# EEG.net
KiCad netlist of a schematic drawn in EAGLE
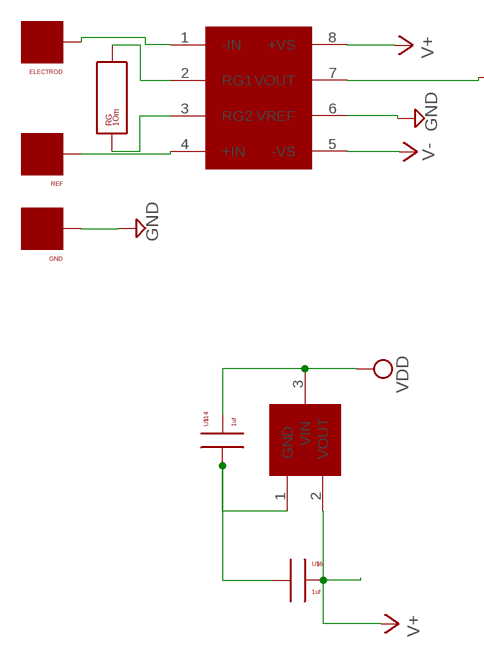
[diagram p0: schematic, sheet 1, part 1 of 2]
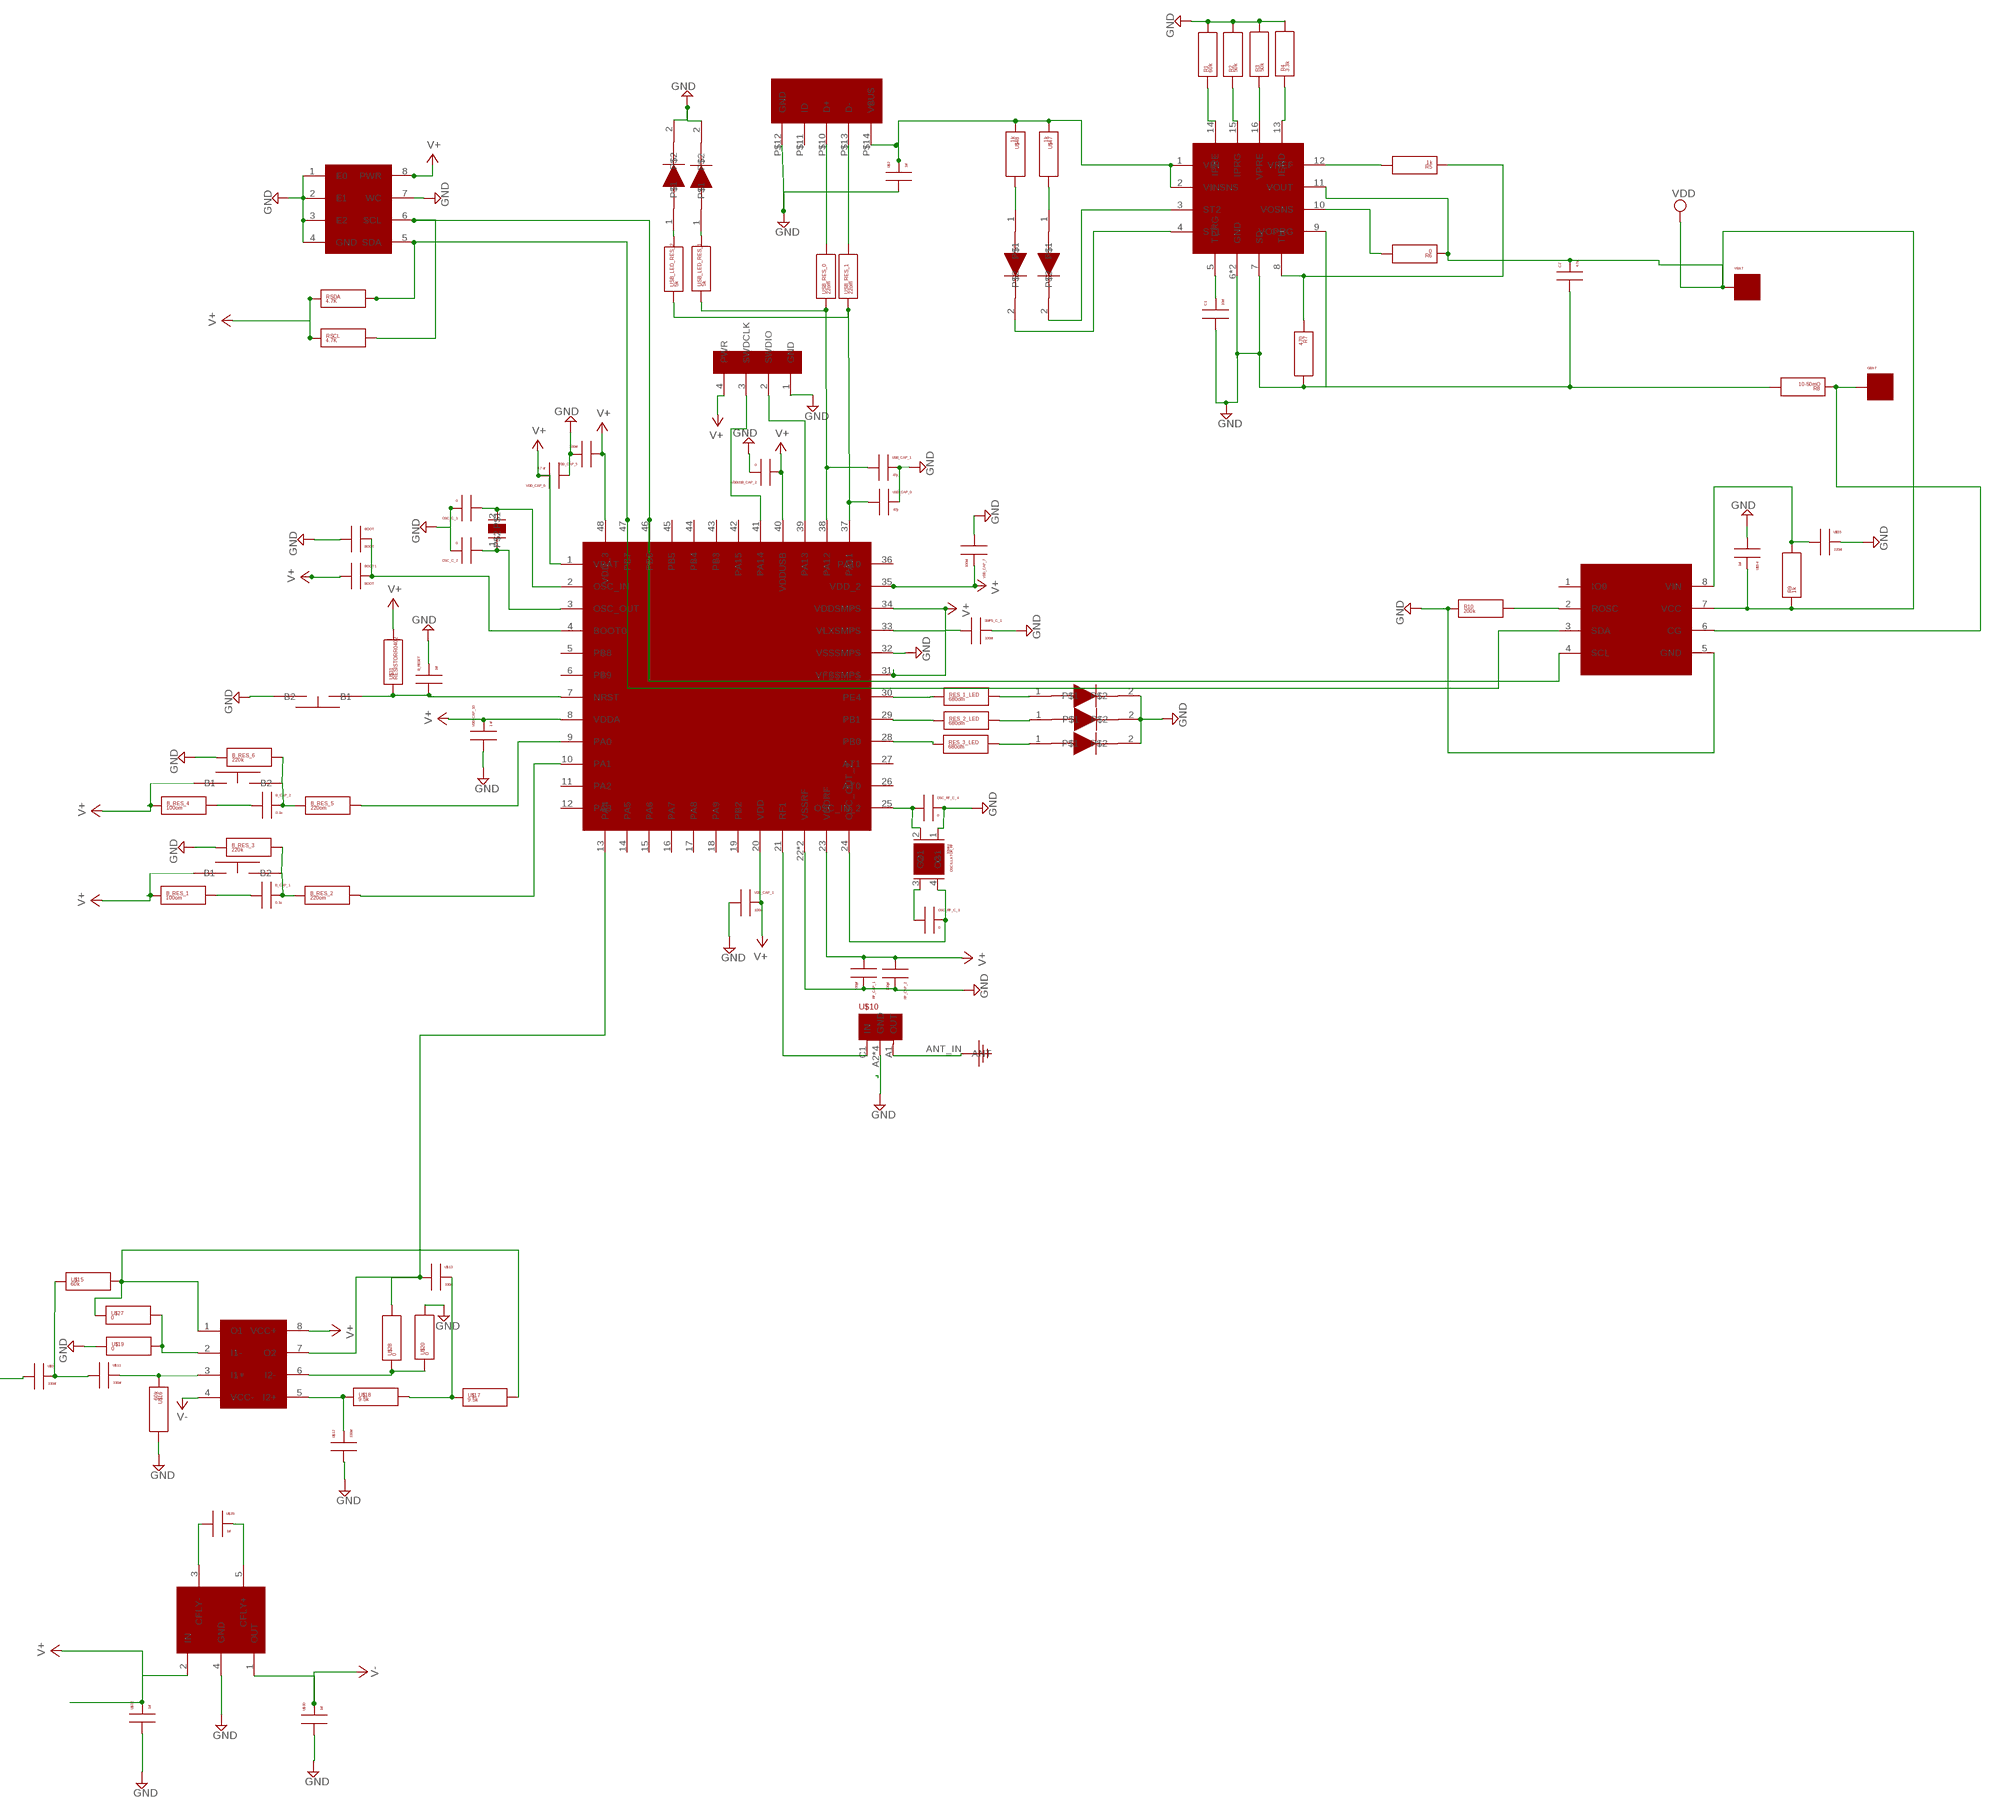
[diagram p1: schematic, sheet 1, part 2 of 2]

(export (version "E")
  (design (tool "Eeschema 10.0.6"))
  (components
    (comp (ref "BOOT")
      (value "BOOT")
      (footprint "eagle-import:C0402")
      (libsource (lib "eagle-import") (part "CAPACITORC0402"))
    )
    (comp (ref "BOOT1")
      (value "BOOT")
      (footprint "eagle-import:C0402")
      (libsource (lib "eagle-import") (part "CAPACITORC0402"))
    )
    (comp (ref "BUTTON1")
      (value "BUTTON")
      (footprint "eagle-import:BUTTON")
      (libsource (lib "eagle-import") (part "BUTTON"))
    )
    (comp (ref "BUTTON2")
      (value "BUTTON")
      (footprint "eagle-import:BUTTON")
      (libsource (lib "eagle-import") (part "BUTTON"))
    )
    (comp (ref "B_CAP_1")
      (value "0.1u")
      (footprint "eagle-import:C0402")
      (libsource (lib "eagle-import") (part "CAPACITORC0402"))
    )
    (comp (ref "B_CAP_2")
      (value "0.1u")
      (footprint "eagle-import:C0402")
      (libsource (lib "eagle-import") (part "CAPACITORC0402"))
    )
    (comp (ref "B_RESET")
      (value "1uf")
      (footprint "eagle-import:C0402")
      (libsource (lib "eagle-import") (part "CAPACITORC0402"))
    )
    (comp (ref "B_RES_1")
      (value "100om")
      (footprint "eagle-import:R0402")
      (libsource (lib "eagle-import") (part "RESISTORR0402"))
    )
    (comp (ref "B_RES_2")
      (value "220om")
      (footprint "eagle-import:R0402")
      (libsource (lib "eagle-import") (part "RESISTORR0402"))
    )
    (comp (ref "B_RES_3")
      (value "220k")
      (footprint "eagle-import:R0402")
      (libsource (lib "eagle-import") (part "RESISTORR0402"))
    )
    (comp (ref "B_RES_4")
      (value "100om")
      (footprint "eagle-import:R0402")
      (libsource (lib "eagle-import") (part "RESISTORR0402"))
    )
    (comp (ref "B_RES_5")
      (value "220om")
      (footprint "eagle-import:R0402")
      (libsource (lib "eagle-import") (part "RESISTORR0402"))
    )
    (comp (ref "B_RES_6")
      (value "220k")
      (footprint "eagle-import:R0402")
      (libsource (lib "eagle-import") (part "RESISTORR0402"))
    )
    (comp (ref "C1")
      (value "10nf")
      (footprint "eagle-import:C0402")
      (libsource (lib "eagle-import") (part "CAPACITORC0402"))
    )
    (comp (ref "C2")
      (value "4.7uf")
      (footprint "eagle-import:C0402")
      (libsource (lib "eagle-import") (part "CAPACITORC0402"))
    )
    (comp (ref "ELECTROD")
      (value "PIN-1")
      (footprint "eagle-import:PIN-1")
      (libsource (lib "eagle-import") (part "PIN-1"))
    )
    (comp (ref "GBAT")
      (value "PIN-1")
      (footprint "eagle-import:PIN-1")
      (libsource (lib "eagle-import") (part "PIN-1"))
    )
    (comp (ref "GND")
      (value "PIN-1")
      (footprint "eagle-import:PIN-1")
      (libsource (lib "eagle-import") (part "PIN-1"))
    )
    (comp (ref "LED_1")
      (value "LED")
      (footprint "eagle-import:R0402")
      (libsource (lib "eagle-import") (part "LED"))
    )
    (comp (ref "LED_2")
      (value "LED")
      (footprint "eagle-import:R0402")
      (libsource (lib "eagle-import") (part "LED"))
    )
    (comp (ref "LED_3")
      (value "LED")
      (footprint "eagle-import:R0402")
      (libsource (lib "eagle-import") (part "LED"))
    )
    (comp (ref "OSCILLATOR_RF")
      (value "32mhz")
      (footprint "eagle-import:NX2520SA")
      (libsource (lib "eagle-import") (part "NX2520SA"))
    )
    (comp (ref "OSC_C_1")
      (value "0")
      (footprint "eagle-import:C0402")
      (libsource (lib "eagle-import") (part "CAPACITORC0402"))
    )
    (comp (ref "OSC_C_2")
      (value "0")
      (footprint "eagle-import:C0402")
      (libsource (lib "eagle-import") (part "CAPACITORC0402"))
    )
    (comp (ref "OSC_RF_C_3")
      (value "0")
      (footprint "eagle-import:C0402")
      (libsource (lib "eagle-import") (part "CAPACITORC0402"))
    )
    (comp (ref "OSC_RF_C_4")
      (value "0")
      (footprint "eagle-import:C0402")
      (libsource (lib "eagle-import") (part "CAPACITORC0402"))
    )
    (comp (ref "R1")
      (value "60k")
      (footprint "eagle-import:R0402")
      (libsource (lib "eagle-import") (part "RESISTORR0402"))
    )
    (comp (ref "R2")
      (value "50k")
      (footprint "eagle-import:R0402")
      (libsource (lib "eagle-import") (part "RESISTORR0402"))
    )
    (comp (ref "R3")
      (value "50k")
      (footprint "eagle-import:R0402")
      (libsource (lib "eagle-import") (part "RESISTORR0402"))
    )
    (comp (ref "R4")
      (value "3.3k")
      (footprint "eagle-import:R0402")
      (libsource (lib "eagle-import") (part "RESISTORR0402"))
    )
    (comp (ref "R5")
      (value "1k")
      (footprint "eagle-import:R0402")
      (libsource (lib "eagle-import") (part "RESISTORR0402"))
    )
    (comp (ref "R6")
      (value "0")
      (footprint "eagle-import:R0402")
      (libsource (lib "eagle-import") (part "RESISTORR0402"))
    )
    (comp (ref "R7")
      (value "470")
      (footprint "eagle-import:R0402")
      (libsource (lib "eagle-import") (part "RESISTORR0402"))
    )
    (comp (ref "R8")
      (value "10-50mO")
      (footprint "eagle-import:R0402")
      (libsource (lib "eagle-import") (part "RESISTORR0402"))
    )
    (comp (ref "R9")
      (value "1k")
      (footprint "eagle-import:R0402")
      (libsource (lib "eagle-import") (part "RESISTORR0402"))
    )
    (comp (ref "R10")
      (value "200k")
      (footprint "eagle-import:R0402")
      (libsource (lib "eagle-import") (part "RESISTORR0402"))
    )
    (comp (ref "REF")
      (value "PIN-1")
      (footprint "eagle-import:PIN-1")
      (libsource (lib "eagle-import") (part "PIN-1"))
    )
    (comp (ref "RES_1_LED")
      (value "680om")
      (footprint "eagle-import:R0402")
      (libsource (lib "eagle-import") (part "RESISTORR0402"))
    )
    (comp (ref "RES_2_LED")
      (value "680om")
      (footprint "eagle-import:R0402")
      (libsource (lib "eagle-import") (part "RESISTORR0402"))
    )
    (comp (ref "RES_3_LED")
      (value "680om")
      (footprint "eagle-import:R0402")
      (libsource (lib "eagle-import") (part "RESISTORR0402"))
    )
    (comp (ref "RF_CAP_1")
      (value "100pf")
      (footprint "eagle-import:C0402")
      (libsource (lib "eagle-import") (part "CAPACITORC0402"))
    )
    (comp (ref "RF_CAP_2")
      (value "100pf")
      (footprint "eagle-import:C0402")
      (libsource (lib "eagle-import") (part "CAPACITORC0402"))
    )
    (comp (ref "RG")
      (value "1Om")
      (footprint "eagle-import:R0402")
      (libsource (lib "eagle-import") (part "RESISTORR0402"))
    )
    (comp (ref "RSCL")
      (value "4.7K")
      (footprint "eagle-import:R0402")
      (libsource (lib "eagle-import") (part "RESISTORR0402"))
    )
    (comp (ref "RSDA")
      (value "4.7K")
      (footprint "eagle-import:R0402")
      (libsource (lib "eagle-import") (part "RESISTORR0402"))
    )
    (comp (ref "SMPS_C_1")
      (value "100nf")
      (footprint "eagle-import:C0402")
      (libsource (lib "eagle-import") (part "CAPACITORC0402"))
    )
    (comp (ref "U$1")
      (value "STM32WB55")
      (footprint "eagle-import:STM32WB55")
      (libsource (lib "eagle-import") (part "STM32WB55"))
    )
    (comp (ref "U$2")
      (value "1uf")
      (footprint "eagle-import:C0402")
      (libsource (lib "eagle-import") (part "CAPACITORC0402"))
    )
    (comp (ref "U$3")
      (value "ANT")
      (footprint "eagle-import:ANT")
      (libsource (lib "eagle-import") (part "ANT"))
    )
    (comp (ref "U$4")
      (value "AD8422")
      (footprint "eagle-import:AD8422")
      (libsource (lib "eagle-import") (part "AD8422"))
    )
    (comp (ref "U$5")
      (value "TPS60403")
      (footprint "eagle-import:TPS60403")
      (libsource (lib "eagle-import") (part "TPS60403"))
    )
    (comp (ref "U$6")
      (value "1uf")
      (footprint "eagle-import:C0402")
      (libsource (lib "eagle-import") (part "CAPACITORC0402"))
    )
    (comp (ref "U$7")
      (value "LM358")
      (footprint "eagle-import:LM358")
      (libsource (lib "eagle-import") (part "LM358"))
    )
    (comp (ref "U$8")
      (value "MCP1703")
      (footprint "eagle-import:MCP1703")
      (libsource (lib "eagle-import") (part "MCP1703"))
    )
    (comp (ref "U$9")
      (value "330nf")
      (footprint "eagle-import:C0402")
      (libsource (lib "eagle-import") (part "CAPACITORC0402"))
    )
    (comp (ref "U$10")
      (value "MLPF-WB55-01E3DEFAULT")
      (footprint "eagle-import:MLPF-WB55-01E3")
      (libsource (lib "eagle-import") (part "MLPF-WB55-01E3DEFAULT"))
    )
    (comp (ref "U$11")
      (value "330nf")
      (footprint "eagle-import:C0402")
      (libsource (lib "eagle-import") (part "CAPACITORC0402"))
    )
    (comp (ref "U$12")
      (value "330nf")
      (footprint "eagle-import:C0402")
      (libsource (lib "eagle-import") (part "CAPACITORC0402"))
    )
    (comp (ref "U$13")
      (value "330nf")
      (footprint "eagle-import:C0402")
      (libsource (lib "eagle-import") (part "CAPACITORC0402"))
    )
    (comp (ref "U$14")
      (value "1uf")
      (footprint "eagle-import:C0402")
      (libsource (lib "eagle-import") (part "CAPACITORC0402"))
    )
    (comp (ref "U$15")
      (value "60k")
      (footprint "eagle-import:R0402")
      (libsource (lib "eagle-import") (part "RESISTORR0402"))
    )
    (comp (ref "U$16")
      (value "60k")
      (footprint "eagle-import:R0402")
      (libsource (lib "eagle-import") (part "RESISTORR0402"))
    )
    (comp (ref "U$17")
      (value "9.5k")
      (footprint "eagle-import:R0402")
      (libsource (lib "eagle-import") (part "RESISTORR0402"))
    )
    (comp (ref "U$18")
      (value "9.5k")
      (footprint "eagle-import:R0402")
      (libsource (lib "eagle-import") (part "RESISTORR0402"))
    )
    (comp (ref "U$19")
      (value "0")
      (footprint "eagle-import:R0402")
      (libsource (lib "eagle-import") (part "RESISTORR0402"))
    )
    (comp (ref "U$20")
      (value "0")
      (footprint "eagle-import:R0402")
      (libsource (lib "eagle-import") (part "RESISTORR0402"))
    )
    (comp (ref "U$21")
      (value "M24M01")
      (footprint "eagle-import:M24M01")
      (libsource (lib "eagle-import") (part "M24M01"))
    )
    (comp (ref "U$22")
      (value "USBUSBT")
      (footprint "eagle-import:USBT")
      (libsource (lib "eagle-import") (part "USBUSBT"))
    )
    (comp (ref "U$23")
      (value "SWDSWDD")
      (footprint "eagle-import:SWD")
      (libsource (lib "eagle-import") (part "SWDSWDD"))
    )
    (comp (ref "U$24")
      (value "STC3100")
      (footprint "eagle-import:STC3100")
      (libsource (lib "eagle-import") (part "STC3100"))
    )
    (comp (ref "U$25")
      (value "L6924D")
      (footprint "eagle-import:L6924D")
      (libsource (lib "eagle-import") (part "L6924D"))
    )
    (comp (ref "U$26")
      (value "BUTTON")
      (footprint "eagle-import:BUTTON")
      (libsource (lib "eagle-import") (part "BUTTON"))
    )
    (comp (ref "U$27")
      (value "0")
      (footprint "eagle-import:R0402")
      (libsource (lib "eagle-import") (part "RESISTORR0402"))
    )
    (comp (ref "U$28")
      (value "0")
      (footprint "eagle-import:R0402")
      (libsource (lib "eagle-import") (part "RESISTORR0402"))
    )
    (comp (ref "U$29")
      (value "1uf")
      (footprint "eagle-import:C0402")
      (libsource (lib "eagle-import") (part "CAPACITORC0402"))
    )
    (comp (ref "U$30")
      (value "1uf")
      (footprint "eagle-import:C0402")
      (libsource (lib "eagle-import") (part "CAPACITORC0402"))
    )
    (comp (ref "U$31")
      (value "RESISTORR0402")
      (footprint "eagle-import:R0402")
      (libsource (lib "eagle-import") (part "RESISTORR0402"))
    )
    (comp (ref "U$32")
      (value "1uf")
      (footprint "eagle-import:C0402")
      (libsource (lib "eagle-import") (part "CAPACITORC0402"))
    )
    (comp (ref "U$33")
      (value "OSC_32KH")
      (footprint "eagle-import:RESM2012X60N")
      (libsource (lib "eagle-import") (part "OSC_32KH"))
    )
    (comp (ref "U$47")
      (value "1k")
      (footprint "eagle-import:R0402")
      (libsource (lib "eagle-import") (part "RESISTORR0402"))
    )
    (comp (ref "U$48")
      (value "1k")
      (footprint "eagle-import:R0402")
      (libsource (lib "eagle-import") (part "RESISTORR0402"))
    )
    (comp (ref "U$49")
      (value "LED")
      (footprint "eagle-import:R0402")
      (libsource (lib "eagle-import") (part "LED"))
    )
    (comp (ref "U$50")
      (value "LED")
      (footprint "eagle-import:R0402")
      (libsource (lib "eagle-import") (part "LED"))
    )
    (comp (ref "U$54")
      (value "1uf")
      (footprint "eagle-import:C0402")
      (libsource (lib "eagle-import") (part "CAPACITORC0402"))
    )
    (comp (ref "U$55")
      (value "220nf")
      (footprint "eagle-import:C0402")
      (libsource (lib "eagle-import") (part "CAPACITORC0402"))
    )
    (comp (ref "USB_CAP_0")
      (value "47p")
      (footprint "eagle-import:C0402")
      (libsource (lib "eagle-import") (part "CAPACITORC0402"))
    )
    (comp (ref "USB_CAP_1")
      (value "47p")
      (footprint "eagle-import:C0402")
      (libsource (lib "eagle-import") (part "CAPACITORC0402"))
    )
    (comp (ref "USB_LED_1")
      (value "LED")
      (footprint "eagle-import:R0402")
      (libsource (lib "eagle-import") (part "LED"))
    )
    (comp (ref "USB_LED_2")
      (value "LED")
      (footprint "eagle-import:R0402")
      (libsource (lib "eagle-import") (part "LED"))
    )
    (comp (ref "USB_LED_RES_1")
      (value "5k")
      (footprint "eagle-import:R0402")
      (libsource (lib "eagle-import") (part "RESISTORR0402"))
    )
    (comp (ref "USB_LED_RES_2")
      (value "5k")
      (footprint "eagle-import:R0402")
      (libsource (lib "eagle-import") (part "RESISTORR0402"))
    )
    (comp (ref "USB_RES_0")
      (value "22om")
      (footprint "eagle-import:R0402")
      (libsource (lib "eagle-import") (part "RESISTORR0402"))
    )
    (comp (ref "USB_RES_1")
      (value "22om")
      (footprint "eagle-import:R0402")
      (libsource (lib "eagle-import") (part "RESISTORR0402"))
    )
    (comp (ref "VBAT")
      (value "PIN-1")
      (footprint "eagle-import:PIN-1")
      (libsource (lib "eagle-import") (part "PIN-1"))
    )
    (comp (ref "VDDUSB_CAP_2")
      (value "0")
      (footprint "eagle-import:C0402")
      (libsource (lib "eagle-import") (part "CAPACITORC0402"))
    )
    (comp (ref "VDD_CAP_1")
      (value "100nf")
      (footprint "eagle-import:C0402")
      (libsource (lib "eagle-import") (part "CAPACITORC0402"))
    )
    (comp (ref "VDD_CAP_5")
      (value "100nf")
      (footprint "eagle-import:C0402")
      (libsource (lib "eagle-import") (part "CAPACITORC0402"))
    )
    (comp (ref "VDD_CAP_6")
      (value "4.7 uf")
      (footprint "eagle-import:C0402")
      (libsource (lib "eagle-import") (part "CAPACITORC0402"))
    )
    (comp (ref "VDD_CAP_7")
      (value "100nf")
      (footprint "eagle-import:C0402")
      (libsource (lib "eagle-import") (part "CAPACITORC0402"))
    )
    (comp (ref "VDD_CAP_10")
      (value "1 uf")
      (footprint "eagle-import:C0402")
      (libsource (lib "eagle-import") (part "CAPACITORC0402"))
    )
  )
  (nets
    (net (code "1") (name "GND") (class "Default")
      (node (ref "BOOT") (pin "1") (pinfunction "1_1") (pintype "bidirectional"))
      (node (ref "B_RESET") (pin "2") (pinfunction "2_2") (pintype "bidirectional"))
      (node (ref "B_RES_3") (pin "1") (pinfunction "1_1") (pintype "bidirectional"))
      (node (ref "B_RES_6") (pin "1") (pinfunction "1_1") (pintype "bidirectional"))
      (node (ref "C1") (pin "1") (pinfunction "1_1") (pintype "bidirectional"))
      (node (ref "C2") (pin "1") (pinfunction "1_1") (pintype "bidirectional"))
      (node (ref "GND") (pin "P$1") (pinfunction "PIN_P$1") (pintype "bidirectional"))
      (node (ref "LED_1") (pin "2") (pinfunction "P$2_2") (pintype "bidirectional"))
      (node (ref "LED_2") (pin "2") (pinfunction "P$2_2") (pintype "bidirectional"))
      (node (ref "LED_3") (pin "2") (pinfunction "P$2_2") (pintype "bidirectional"))
      (node (ref "OSCILLATOR_RF") (pin "1") (pinfunction "G1_1") (pintype "bidirectional"))
      (node (ref "OSC_C_1") (pin "2") (pinfunction "2_2") (pintype "bidirectional"))
      (node (ref "OSC_C_2") (pin "2") (pinfunction "2_2") (pintype "bidirectional"))
      (node (ref "OSC_RF_C_4") (pin "2") (pinfunction "2_2") (pintype "bidirectional"))
      (node (ref "R1") (pin "2") (pinfunction "2_2") (pintype "bidirectional"))
      (node (ref "R10") (pin "1") (pinfunction "1_1") (pintype "bidirectional"))
      (node (ref "R2") (pin "2") (pinfunction "2_2") (pintype "bidirectional"))
      (node (ref "R3") (pin "2") (pinfunction "2_2") (pintype "bidirectional"))
      (node (ref "R4") (pin "2") (pinfunction "2_2") (pintype "bidirectional"))
      (node (ref "R7") (pin "2") (pinfunction "2_2") (pintype "bidirectional"))
      (node (ref "R8") (pin "2") (pinfunction "2_2") (pintype "bidirectional"))
      (node (ref "RF_CAP_1") (pin "2") (pinfunction "2_2") (pintype "bidirectional"))
      (node (ref "RF_CAP_2") (pin "2") (pinfunction "2_2") (pintype "bidirectional"))
      (node (ref "SMPS_C_1") (pin "2") (pinfunction "2_2") (pintype "bidirectional"))
      (node (ref "U$1") (pin "22") (pinfunction "VSSRF_22") (pintype "bidirectional"))
      (node (ref "U$1") (pin "32") (pinfunction "VSSSMPS_32") (pintype "bidirectional"))
      (node (ref "U$1") (pin "49") (pinfunction "VSSRF_49") (pintype "bidirectional"))
      (node (ref "U$10") (pin "A2") (pinfunction "GND_A2") (pintype "bidirectional"))
      (node (ref "U$10") (pin "B1") (pinfunction "GND_B1") (pintype "bidirectional"))
      (node (ref "U$10") (pin "B2") (pinfunction "GND_B2") (pintype "bidirectional"))
      (node (ref "U$10") (pin "C2") (pinfunction "GND_C2") (pintype "bidirectional"))
      (node (ref "U$12") (pin "1") (pinfunction "1_1") (pintype "bidirectional"))
      (node (ref "U$16") (pin "2") (pinfunction "2_2") (pintype "bidirectional"))
      (node (ref "U$19") (pin "1") (pinfunction "1_1") (pintype "bidirectional"))
      (node (ref "U$2") (pin "1") (pinfunction "1_1") (pintype "bidirectional"))
      (node (ref "U$20") (pin "2") (pinfunction "2_2") (pintype "bidirectional"))
      (node (ref "U$21") (pin "1") (pinfunction "E0_1") (pintype "bidirectional"))
      (node (ref "U$21") (pin "2") (pinfunction "E1_2") (pintype "bidirectional"))
      (node (ref "U$21") (pin "3") (pinfunction "E2_3") (pintype "bidirectional"))
      (node (ref "U$21") (pin "4") (pinfunction "GND_4") (pintype "bidirectional"))
      (node (ref "U$21") (pin "7") (pinfunction "WC_7") (pintype "bidirectional"))
      (node (ref "U$22") (pin "P$12") (pinfunction "GND_P$12") (pintype "bidirectional"))
      (node (ref "U$23") (pin "1") (pinfunction "GND_1") (pintype "bidirectional"))
      (node (ref "U$24") (pin "5") (pinfunction "GND_5") (pintype "bidirectional"))
      (node (ref "U$25") (pin "17") (pinfunction "GND_17") (pintype "bidirectional"))
      (node (ref "U$25") (pin "6") (pinfunction "GND_6") (pintype "bidirectional"))
      (node (ref "U$25") (pin "7") (pinfunction "SD_7") (pintype "bidirectional"))
      (node (ref "U$25") (pin "9") (pinfunction "VOPRG_9") (pintype "bidirectional"))
      (node (ref "U$26") (pin "2") (pinfunction "B2_2") (pintype "bidirectional"))
      (node (ref "U$30") (pin "1") (pinfunction "1_1") (pintype "bidirectional"))
      (node (ref "U$32") (pin "1") (pinfunction "1_1") (pintype "bidirectional"))
      (node (ref "U$4") (pin "6") (pinfunction "VREF_6") (pintype "bidirectional"))
      (node (ref "U$5") (pin "4") (pinfunction "GND_4") (pintype "bidirectional"))
      (node (ref "U$54") (pin "1") (pinfunction "1_1") (pintype "bidirectional"))
      (node (ref "U$55") (pin "2") (pinfunction "2_2") (pintype "bidirectional"))
      (node (ref "USB_CAP_0") (pin "2") (pinfunction "2_2") (pintype "bidirectional"))
      (node (ref "USB_CAP_1") (pin "2") (pinfunction "2_2") (pintype "bidirectional"))
      (node (ref "USB_LED_1") (pin "2") (pinfunction "P$2_2") (pintype "bidirectional"))
      (node (ref "USB_LED_2") (pin "2") (pinfunction "P$2_2") (pintype "bidirectional"))
      (node (ref "VDDUSB_CAP_2") (pin "2") (pinfunction "2_2") (pintype "bidirectional"))
      (node (ref "VDD_CAP_1") (pin "1") (pinfunction "1_1") (pintype "bidirectional"))
      (node (ref "VDD_CAP_10") (pin "1") (pinfunction "1_1") (pintype "bidirectional"))
      (node (ref "VDD_CAP_5") (pin "2") (pinfunction "2_2") (pintype "bidirectional"))
      (node (ref "VDD_CAP_6") (pin "1") (pinfunction "1_1") (pintype "bidirectional"))
      (node (ref "VDD_CAP_7") (pin "1") (pinfunction "1_1") (pintype "bidirectional"))
    )
    (net (code "2") (name "Net-(BUTTON1-B2)") (class "Default")
      (node (ref "BUTTON1") (pin "2") (pinfunction "B2_2") (pintype "bidirectional"))
      (node (ref "B_CAP_2") (pin "2") (pinfunction "2_2") (pintype "bidirectional"))
      (node (ref "B_RES_5") (pin "1") (pinfunction "1_1") (pintype "bidirectional"))
      (node (ref "B_RES_6") (pin "2") (pinfunction "2_2") (pintype "bidirectional"))
    )
    (net (code "3") (name "Net-(BUTTON2-B2)") (class "Default")
      (node (ref "BUTTON2") (pin "2") (pinfunction "B2_2") (pintype "bidirectional"))
      (node (ref "B_CAP_1") (pin "2") (pinfunction "2_2") (pintype "bidirectional"))
      (node (ref "B_RES_2") (pin "1") (pinfunction "1_1") (pintype "bidirectional"))
      (node (ref "B_RES_3") (pin "2") (pinfunction "2_2") (pintype "bidirectional"))
    )
    (net (code "4") (name "Net-(B_CAP_1-Pad1)") (class "Default")
      (node (ref "B_CAP_1") (pin "1") (pinfunction "1_1") (pintype "bidirectional"))
      (node (ref "B_RES_1") (pin "2") (pinfunction "2_2") (pintype "bidirectional"))
    )
    (net (code "5") (name "Net-(B_CAP_2-Pad1)") (class "Default")
      (node (ref "B_CAP_2") (pin "1") (pinfunction "1_1") (pintype "bidirectional"))
      (node (ref "B_RES_4") (pin "2") (pinfunction "2_2") (pintype "bidirectional"))
    )
    (net (code "6") (name "Net-(ELECTROD-PIN)") (class "Default")
      (node (ref "ELECTROD") (pin "P$1") (pinfunction "PIN_P$1") (pintype "bidirectional"))
      (node (ref "U$4") (pin "1") (pinfunction "-IN_1") (pintype "bidirectional"))
    )
    (net (code "7") (name "Net-(GBAT-PIN)") (class "Default")
      (node (ref "GBAT") (pin "P$1") (pinfunction "PIN_P$1") (pintype "bidirectional"))
      (node (ref "R8") (pin "1") (pinfunction "1_1") (pintype "bidirectional"))
      (node (ref "U$24") (pin "6") (pinfunction "CG_6") (pintype "bidirectional"))
    )
    (net (code "8") (name "Net-(LED_1-P$1)") (class "Default")
      (node (ref "LED_1") (pin "1") (pinfunction "P$1_1") (pintype "bidirectional"))
      (node (ref "RES_1_LED") (pin "2") (pinfunction "2_2") (pintype "bidirectional"))
    )
    (net (code "9") (name "Net-(LED_2-P$1)") (class "Default")
      (node (ref "LED_2") (pin "1") (pinfunction "P$1_1") (pintype "bidirectional"))
      (node (ref "RES_2_LED") (pin "2") (pinfunction "2_2") (pintype "bidirectional"))
    )
    (net (code "10") (name "Net-(LED_3-P$1)") (class "Default")
      (node (ref "LED_3") (pin "1") (pinfunction "P$1_1") (pintype "bidirectional"))
      (node (ref "RES_3_LED") (pin "2") (pinfunction "2_2") (pintype "bidirectional"))
    )
    (net (code "11") (name "Net-(OSCILLATOR_RF-G2)") (class "Default")
      (node (ref "OSCILLATOR_RF") (pin "3") (pinfunction "G2_3") (pintype "bidirectional"))
      (node (ref "OSC_RF_C_3") (pin "1") (pinfunction "1_1") (pintype "bidirectional"))
    )
    (net (code "12") (name "Net-(OSCILLATOR_RF-O1)") (class "Default")
      (node (ref "OSCILLATOR_RF") (pin "2") (pinfunction "O1_2") (pintype "bidirectional"))
      (node (ref "OSC_RF_C_4") (pin "1") (pinfunction "1_1") (pintype "bidirectional"))
      (node (ref "U$1") (pin "25") (pinfunction "OSC_IN_2_25") (pintype "bidirectional"))
    )
    (net (code "13") (name "Net-(OSCILLATOR_RF-O2)") (class "Default")
      (node (ref "OSCILLATOR_RF") (pin "4") (pinfunction "O2_4") (pintype "bidirectional"))
      (node (ref "OSC_RF_C_3") (pin "2") (pinfunction "2_2") (pintype "bidirectional"))
      (node (ref "U$1") (pin "24") (pinfunction "OSC_OUT_2_24") (pintype "bidirectional"))
    )
    (net (code "14") (name "Net-(REF-PIN)") (class "Default")
      (node (ref "REF") (pin "P$1") (pinfunction "PIN_P$1") (pintype "bidirectional"))
      (node (ref "U$4") (pin "4") (pinfunction "+IN_4") (pintype "bidirectional"))
    )
    (net (code "15") (name "Net-(U$1-BOOT0)") (class "Default")
      (node (ref "BOOT") (pin "2") (pinfunction "2_2") (pintype "bidirectional"))
      (node (ref "BOOT1") (pin "2") (pinfunction "2_2") (pintype "bidirectional"))
      (node (ref "U$1") (pin "4") (pinfunction "BOOT0_4") (pintype "bidirectional"))
    )
    (net (code "16") (name "Net-(U$1-NRST)") (class "Default")
      (node (ref "B_RESET") (pin "1") (pinfunction "1_1") (pintype "bidirectional"))
      (node (ref "U$1") (pin "7") (pinfunction "NRST_7") (pintype "bidirectional"))
      (node (ref "U$26") (pin "1") (pinfunction "B1_1") (pintype "bidirectional"))
      (node (ref "U$31") (pin "1") (pinfunction "1_1") (pintype "bidirectional"))
    )
    (net (code "17") (name "Net-(U$1-OSC_IN)") (class "Default")
      (node (ref "OSC_C_1") (pin "1") (pinfunction "1_1") (pintype "bidirectional"))
      (node (ref "U$1") (pin "2") (pinfunction "OSC_IN_2") (pintype "bidirectional"))
      (node (ref "U$33") (pin "2") (pinfunction "P$2_2") (pintype "bidirectional"))
    )
    (net (code "18") (name "Net-(U$1-OSC_OUT)") (class "Default")
      (node (ref "OSC_C_2") (pin "1") (pinfunction "1_1") (pintype "bidirectional"))
      (node (ref "U$1") (pin "3") (pinfunction "OSC_OUT_3") (pintype "bidirectional"))
      (node (ref "U$33") (pin "1") (pinfunction "P$1_1") (pintype "bidirectional"))
    )
    (net (code "19") (name "Net-(U$1-PA0)") (class "Default")
      (node (ref "B_RES_5") (pin "2") (pinfunction "2_2") (pintype "bidirectional"))
      (node (ref "U$1") (pin "9") (pinfunction "PA0_9") (pintype "bidirectional"))
    )
    (net (code "20") (name "Net-(U$1-PA1)") (class "Default")
      (node (ref "B_RES_2") (pin "2") (pinfunction "2_2") (pintype "bidirectional"))
      (node (ref "U$1") (pin "10") (pinfunction "PA1_10") (pintype "bidirectional"))
    )
    (net (code "21") (name "Net-(U$1-PA4)") (class "Default")
      (node (ref "U$1") (pin "13") (pinfunction "PA4_13") (pintype "bidirectional"))
      (node (ref "U$13") (pin "1") (pinfunction "1_1") (pintype "bidirectional"))
      (node (ref "U$28") (pin "2") (pinfunction "2_2") (pintype "bidirectional"))
      (node (ref "U$7") (pin "7") (pinfunction "O2_7") (pintype "bidirectional"))
    )
    (net (code "22") (name "Net-(U$1-PA11)") (class "Default")
      (node (ref "U$1") (pin "37") (pinfunction "PA11_37") (pintype "bidirectional"))
      (node (ref "USB_CAP_0") (pin "1") (pinfunction "1_1") (pintype "bidirectional"))
      (node (ref "USB_LED_RES_2") (pin "1") (pinfunction "1_1") (pintype "bidirectional"))
      (node (ref "USB_RES_1") (pin "1") (pinfunction "1_1") (pintype "bidirectional"))
    )
    (net (code "23") (name "Net-(U$1-PA12)") (class "Default")
      (node (ref "U$1") (pin "38") (pinfunction "PA12_38") (pintype "bidirectional"))
      (node (ref "USB_CAP_1") (pin "1") (pinfunction "1_1") (pintype "bidirectional"))
      (node (ref "USB_LED_RES_1") (pin "1") (pinfunction "1_1") (pintype "bidirectional"))
      (node (ref "USB_RES_0") (pin "1") (pinfunction "1_1") (pintype "bidirectional"))
    )
    (net (code "24") (name "Net-(U$1-PA13)") (class "Default")
      (node (ref "U$1") (pin "39") (pinfunction "PA13_39") (pintype "bidirectional"))
      (node (ref "U$23") (pin "2") (pinfunction "SWDIO_2") (pintype "bidirectional"))
    )
    (net (code "25") (name "Net-(U$1-PA14)") (class "Default")
      (node (ref "U$1") (pin "41") (pinfunction "PA14_41") (pintype "bidirectional"))
      (node (ref "U$23") (pin "3") (pinfunction "SWDCLK_3") (pintype "bidirectional"))
    )
    (net (code "26") (name "Net-(U$1-PB0)") (class "Default")
      (node (ref "RES_3_LED") (pin "1") (pinfunction "1_1") (pintype "bidirectional"))
      (node (ref "U$1") (pin "28") (pinfunction "PB0_28") (pintype "bidirectional"))
    )
    (net (code "27") (name "Net-(U$1-PB1)") (class "Default")
      (node (ref "RES_2_LED") (pin "1") (pinfunction "1_1") (pintype "bidirectional"))
      (node (ref "U$1") (pin "29") (pinfunction "PB1_29") (pintype "bidirectional"))
    )
    (net (code "28") (name "Net-(U$1-PB6)") (class "Default")
      (node (ref "RSCL") (pin "2") (pinfunction "2_2") (pintype "bidirectional"))
      (node (ref "U$1") (pin "46") (pinfunction "PB6_46") (pintype "bidirectional"))
      (node (ref "U$21") (pin "6") (pinfunction "SCL_6") (pintype "bidirectional"))
      (node (ref "U$24") (pin "4") (pinfunction "SCL_4") (pintype "bidirectional"))
    )
    (net (code "29") (name "Net-(U$1-PB7)") (class "Default")
      (node (ref "RSDA") (pin "2") (pinfunction "2_2") (pintype "bidirectional"))
      (node (ref "U$1") (pin "47") (pinfunction "PB7_47") (pintype "bidirectional"))
      (node (ref "U$21") (pin "5") (pinfunction "SDA_5") (pintype "bidirectional"))
      (node (ref "U$24") (pin "3") (pinfunction "SDA_3") (pintype "bidirectional"))
    )
    (net (code "30") (name "Net-(U$1-PE4)") (class "Default")
      (node (ref "RES_1_LED") (pin "1") (pinfunction "1_1") (pintype "bidirectional"))
      (node (ref "U$1") (pin "30") (pinfunction "PE4_30") (pintype "bidirectional"))
    )
    (net (code "31") (name "Net-(U$1-RF1)") (class "Default")
      (node (ref "U$1") (pin "21") (pinfunction "RF1_21") (pintype "bidirectional"))
      (node (ref "U$10") (pin "C1") (pinfunction "IN_C1") (pintype "bidirectional"))
    )
    (net (code "32") (name "Net-(U$4-RG1)") (class "Default")
      (node (ref "RG") (pin "2") (pinfunction "2_2") (pintype "bidirectional"))
      (node (ref "U$4") (pin "2") (pinfunction "RG1_2") (pintype "bidirectional"))
    )
    (net (code "33") (name "Net-(U$4-RG2)") (class "Default")
      (node (ref "RG") (pin "1") (pinfunction "1_1") (pintype "bidirectional"))
      (node (ref "U$4") (pin "3") (pinfunction "RG2_3") (pintype "bidirectional"))
    )
    (net (code "34") (name "Net-(U$4-VOUT)") (class "Default")
      (node (ref "U$4") (pin "7") (pinfunction "VOUT_7") (pintype "bidirectional"))
      (node (ref "U$9") (pin "1") (pinfunction "1_1") (pintype "bidirectional"))
    )
    (net (code "35") (name "Net-(U$5-CFLY+)") (class "Default")
      (node (ref "U$29") (pin "2") (pinfunction "2_2") (pintype "bidirectional"))
      (node (ref "U$5") (pin "5") (pinfunction "CFLY+_5") (pintype "bidirectional"))
    )
    (net (code "36") (name "Net-(U$5-CFLY-)") (class "Default")
      (node (ref "U$29") (pin "1") (pinfunction "1_1") (pintype "bidirectional"))
      (node (ref "U$5") (pin "3") (pinfunction "CFLY-_3") (pintype "bidirectional"))
    )
    (net (code "37") (name "Net-(U$7-I1+)") (class "Default")
      (node (ref "U$11") (pin "2") (pinfunction "2_2") (pintype "bidirectional"))
      (node (ref "U$16") (pin "1") (pinfunction "1_1") (pintype "bidirectional"))
      (node (ref "U$7") (pin "3") (pinfunction "I1+_3") (pintype "bidirectional"))
    )
    (net (code "38") (name "Net-(U$7-I1-)") (class "Default")
      (node (ref "U$19") (pin "2") (pinfunction "2_2") (pintype "bidirectional"))
      (node (ref "U$27") (pin "2") (pinfunction "2_2") (pintype "bidirectional"))
      (node (ref "U$7") (pin "2") (pinfunction "I1-_2") (pintype "bidirectional"))
    )
    (net (code "39") (name "Net-(U$7-I2+)") (class "Default")
      (node (ref "U$12") (pin "2") (pinfunction "2_2") (pintype "bidirectional"))
      (node (ref "U$18") (pin "1") (pinfunction "1_1") (pintype "bidirectional"))
      (node (ref "U$7") (pin "5") (pinfunction "I2+_5") (pintype "bidirectional"))
    )
    (net (code "40") (name "Net-(U$7-I2-)") (class "Default")
      (node (ref "U$20") (pin "1") (pinfunction "1_1") (pintype "bidirectional"))
      (node (ref "U$28") (pin "1") (pinfunction "1_1") (pintype "bidirectional"))
      (node (ref "U$7") (pin "6") (pinfunction "I2-_6") (pintype "bidirectional"))
    )
    (net (code "41") (name "Net-(U$7-O1)") (class "Default")
      (node (ref "U$15") (pin "2") (pinfunction "2_2") (pintype "bidirectional"))
      (node (ref "U$17") (pin "2") (pinfunction "2_2") (pintype "bidirectional"))
      (node (ref "U$27") (pin "1") (pinfunction "1_1") (pintype "bidirectional"))
      (node (ref "U$7") (pin "1") (pinfunction "O1_1") (pintype "bidirectional"))
    )
    (net (code "42") (name "Net-(U$8-GND)") (class "Default")
      (node (ref "U$14") (pin "1") (pinfunction "1_1") (pintype "bidirectional"))
      (node (ref "U$6") (pin "1") (pinfunction "1_1") (pintype "bidirectional"))
      (node (ref "U$8") (pin "1") (pinfunction "GND_1") (pintype "bidirectional"))
    )
    (net (code "43") (name "Net-(U$10-OUT)") (class "Default")
      (node (ref "U$10") (pin "A1") (pinfunction "OUT_A1") (pintype "bidirectional"))
      (node (ref "U$3") (pin "ANT_IN") (pinfunction "ANT_ANT_IN") (pintype "bidirectional"))
    )
    (net (code "44") (name "Net-(U$11-Pad1)") (class "Default")
      (node (ref "U$11") (pin "1") (pinfunction "1_1") (pintype "bidirectional"))
      (node (ref "U$15") (pin "1") (pinfunction "1_1") (pintype "bidirectional"))
      (node (ref "U$9") (pin "2") (pinfunction "2_2") (pintype "bidirectional"))
    )
    (net (code "45") (name "Net-(U$13-Pad2)") (class "Default")
      (node (ref "U$13") (pin "2") (pinfunction "2_2") (pintype "bidirectional"))
      (node (ref "U$17") (pin "1") (pinfunction "1_1") (pintype "bidirectional"))
      (node (ref "U$18") (pin "2") (pinfunction "2_2") (pintype "bidirectional"))
    )
    (net (code "46") (name "Net-(U$22-D+)") (class "Default")
      (node (ref "U$22") (pin "P$10") (pinfunction "D+_P$10") (pintype "bidirectional"))
      (node (ref "USB_RES_0") (pin "2") (pinfunction "2_2") (pintype "bidirectional"))
    )
    (net (code "47") (name "Net-(U$22-D-)") (class "Default")
      (node (ref "U$22") (pin "P$13") (pinfunction "D-_P$13") (pintype "bidirectional"))
      (node (ref "USB_RES_1") (pin "2") (pinfunction "2_2") (pintype "bidirectional"))
    )
    (net (code "48") (name "Net-(U$22-VBUS)") (class "Default")
      (node (ref "U$2") (pin "2") (pinfunction "2_2") (pintype "bidirectional"))
      (node (ref "U$22") (pin "P$14") (pinfunction "VBUS_P$14") (pintype "bidirectional"))
      (node (ref "U$25") (pin "1") (pinfunction "VIN_1") (pintype "bidirectional"))
      (node (ref "U$25") (pin "2") (pinfunction "VINSNS_2") (pintype "bidirectional"))
      (node (ref "U$47") (pin "1") (pinfunction "1_1") (pintype "bidirectional"))
      (node (ref "U$48") (pin "1") (pinfunction "1_1") (pintype "bidirectional"))
    )
    (net (code "49") (name "Net-(U$24-ROSC)") (class "Default")
      (node (ref "R10") (pin "2") (pinfunction "2_2") (pintype "bidirectional"))
      (node (ref "U$24") (pin "2") (pinfunction "ROSC_2") (pintype "bidirectional"))
    )
    (net (code "50") (name "Net-(U$24-VIN)") (class "Default")
      (node (ref "R9") (pin "2") (pinfunction "2_2") (pintype "bidirectional"))
      (node (ref "U$24") (pin "8") (pinfunction "VIN_8") (pintype "bidirectional"))
      (node (ref "U$55") (pin "1") (pinfunction "1_1") (pintype "bidirectional"))
    )
    (net (code "51") (name "Net-(U$25-IEND)") (class "Default")
      (node (ref "R4") (pin "1") (pinfunction "1_1") (pintype "bidirectional"))
      (node (ref "U$25") (pin "13") (pinfunction "IEND_13") (pintype "bidirectional"))
    )
    (net (code "52") (name "Net-(U$25-IPRE)") (class "Default")
      (node (ref "R1") (pin "1") (pinfunction "1_1") (pintype "bidirectional"))
      (node (ref "U$25") (pin "14") (pinfunction "IPRE_14") (pintype "bidirectional"))
    )
    (net (code "53") (name "Net-(U$25-IPRG)") (class "Default")
      (node (ref "R2") (pin "1") (pinfunction "1_1") (pintype "bidirectional"))
      (node (ref "U$25") (pin "15") (pinfunction "IPRG_15") (pintype "bidirectional"))
    )
    (net (code "54") (name "Net-(U$25-ST1)") (class "Default")
      (node (ref "U$25") (pin "4") (pinfunction "ST1_4") (pintype "bidirectional"))
      (node (ref "U$50") (pin "2") (pinfunction "P$2_2") (pintype "bidirectional"))
    )
    (net (code "55") (name "Net-(U$25-ST2)") (class "Default")
      (node (ref "U$25") (pin "3") (pinfunction "ST2_3") (pintype "bidirectional"))
      (node (ref "U$49") (pin "2") (pinfunction "P$2_2") (pintype "bidirectional"))
    )
    (net (code "56") (name "Net-(U$25-TH)") (class "Default")
      (node (ref "R5") (pin "1") (pinfunction "1_1") (pintype "bidirectional"))
      (node (ref "R7") (pin "1") (pinfunction "1_1") (pintype "bidirectional"))
      (node (ref "U$25") (pin "8") (pinfunction "TH_8") (pintype "bidirectional"))
    )
    (net (code "57") (name "Net-(U$25-TPRG)") (class "Default")
      (node (ref "C1") (pin "2") (pinfunction "2_2") (pintype "bidirectional"))
      (node (ref "U$25") (pin "5") (pinfunction "TPRG_5") (pintype "bidirectional"))
    )
    (net (code "58") (name "Net-(U$25-VOSNS)") (class "Default")
      (node (ref "R6") (pin "2") (pinfunction "2_2") (pintype "bidirectional"))
      (node (ref "U$25") (pin "10") (pinfunction "VOSNS_10") (pintype "bidirectional"))
    )
    (net (code "59") (name "Net-(U$25-VPRE)") (class "Default")
      (node (ref "R3") (pin "1") (pinfunction "1_1") (pintype "bidirectional"))
      (node (ref "U$25") (pin "16") (pinfunction "VPRE_16") (pintype "bidirectional"))
    )
    (net (code "60") (name "Net-(U$25-VREF)") (class "Default")
      (node (ref "R5") (pin "2") (pinfunction "2_2") (pintype "bidirectional"))
      (node (ref "U$25") (pin "12") (pinfunction "VREF_12") (pintype "bidirectional"))
    )
    (net (code "61") (name "Net-(U$49-P$1)") (class "Default")
      (node (ref "U$47") (pin "2") (pinfunction "2_2") (pintype "bidirectional"))
      (node (ref "U$49") (pin "1") (pinfunction "P$1_1") (pintype "bidirectional"))
    )
    (net (code "62") (name "Net-(U$50-P$1)") (class "Default")
      (node (ref "U$48") (pin "2") (pinfunction "2_2") (pintype "bidirectional"))
      (node (ref "U$50") (pin "1") (pinfunction "P$1_1") (pintype "bidirectional"))
    )
    (net (code "63") (name "Net-(USB_LED_1-P$1)") (class "Default")
      (node (ref "USB_LED_1") (pin "1") (pinfunction "P$1_1") (pintype "bidirectional"))
      (node (ref "USB_LED_RES_1") (pin "2") (pinfunction "2_2") (pintype "bidirectional"))
    )
    (net (code "64") (name "Net-(USB_LED_2-P$1)") (class "Default")
      (node (ref "USB_LED_2") (pin "1") (pinfunction "P$1_1") (pintype "bidirectional"))
      (node (ref "USB_LED_RES_2") (pin "2") (pinfunction "2_2") (pintype "bidirectional"))
    )
    (net (code "65") (name "V+") (class "Default")
      (node (ref "BOOT1") (pin "1") (pinfunction "1_1") (pintype "bidirectional"))
      (node (ref "BUTTON1") (pin "1") (pinfunction "B1_1") (pintype "bidirectional"))
      (node (ref "BUTTON2") (pin "1") (pinfunction "B1_1") (pintype "bidirectional"))
      (node (ref "B_RES_1") (pin "1") (pinfunction "1_1") (pintype "bidirectional"))
      (node (ref "B_RES_4") (pin "1") (pinfunction "1_1") (pintype "bidirectional"))
      (node (ref "RF_CAP_1") (pin "1") (pinfunction "1_1") (pintype "bidirectional"))
      (node (ref "RF_CAP_2") (pin "1") (pinfunction "1_1") (pintype "bidirectional"))
      (node (ref "RSCL") (pin "1") (pinfunction "1_1") (pintype "bidirectional"))
      (node (ref "RSDA") (pin "1") (pinfunction "1_1") (pintype "bidirectional"))
      (node (ref "SMPS_C_1") (pin "1") (pinfunction "1_1") (pintype "bidirectional"))
      (node (ref "U$1") (pin "1") (pinfunction "VBAT_1") (pintype "bidirectional"))
      (node (ref "U$1") (pin "20") (pinfunction "VDD_20") (pintype "bidirectional"))
      (node (ref "U$1") (pin "23") (pinfunction "VDDRF_23") (pintype "bidirectional"))
      (node (ref "U$1") (pin "31") (pinfunction "VFBSMPS_31") (pintype "bidirectional"))
      (node (ref "U$1") (pin "33") (pinfunction "VLXSMPS_33") (pintype "bidirectional"))
      (node (ref "U$1") (pin "34") (pinfunction "VDDSMPS_34") (pintype "bidirectional"))
      (node (ref "U$1") (pin "35") (pinfunction "VDD_2_35") (pintype "bidirectional"))
      (node (ref "U$1") (pin "40") (pinfunction "VDDUSB_40") (pintype "bidirectional"))
      (node (ref "U$1") (pin "48") (pinfunction "VDD_3_48") (pintype "bidirectional"))
      (node (ref "U$1") (pin "8") (pinfunction "VDDA_8") (pintype "bidirectional"))
      (node (ref "U$21") (pin "8") (pinfunction "PWR_8") (pintype "bidirectional"))
      (node (ref "U$23") (pin "4") (pinfunction "PWR_4") (pintype "bidirectional"))
      (node (ref "U$31") (pin "2") (pinfunction "2_2") (pintype "bidirectional"))
      (node (ref "U$32") (pin "2") (pinfunction "2_2") (pintype "bidirectional"))
      (node (ref "U$4") (pin "8") (pinfunction "+VS_8") (pintype "bidirectional"))
      (node (ref "U$5") (pin "2") (pinfunction "IN_2") (pintype "bidirectional"))
      (node (ref "U$6") (pin "2") (pinfunction "2_2") (pintype "bidirectional"))
      (node (ref "U$7") (pin "8") (pinfunction "VCC+_8") (pintype "bidirectional"))
      (node (ref "U$8") (pin "2") (pinfunction "VOUT_2") (pintype "bidirectional"))
      (node (ref "VDDUSB_CAP_2") (pin "1") (pinfunction "1_1") (pintype "bidirectional"))
      (node (ref "VDD_CAP_1") (pin "2") (pinfunction "2_2") (pintype "bidirectional"))
      (node (ref "VDD_CAP_10") (pin "2") (pinfunction "2_2") (pintype "bidirectional"))
      (node (ref "VDD_CAP_5") (pin "1") (pinfunction "1_1") (pintype "bidirectional"))
      (node (ref "VDD_CAP_6") (pin "2") (pinfunction "2_2") (pintype "bidirectional"))
      (node (ref "VDD_CAP_7") (pin "2") (pinfunction "2_2") (pintype "bidirectional"))
    )
    (net (code "66") (name "V-") (class "Default")
      (node (ref "U$30") (pin "2") (pinfunction "2_2") (pintype "bidirectional"))
      (node (ref "U$4") (pin "5") (pinfunction "-VS_5") (pintype "bidirectional"))
      (node (ref "U$5") (pin "1") (pinfunction "OUT_1") (pintype "bidirectional"))
      (node (ref "U$7") (pin "4") (pinfunction "VCC-_4") (pintype "bidirectional"))
    )
    (net (code "67") (name "VDD") (class "Default")
      (node (ref "C2") (pin "2") (pinfunction "2_2") (pintype "bidirectional"))
      (node (ref "R6") (pin "1") (pinfunction "1_1") (pintype "bidirectional"))
      (node (ref "R9") (pin "1") (pinfunction "1_1") (pintype "bidirectional"))
      (node (ref "U$14") (pin "2") (pinfunction "2_2") (pintype "bidirectional"))
      (node (ref "U$24") (pin "7") (pinfunction "VCC_7") (pintype "bidirectional"))
      (node (ref "U$25") (pin "11") (pinfunction "VOUT_11") (pintype "bidirectional"))
      (node (ref "U$54") (pin "2") (pinfunction "2_2") (pintype "bidirectional"))
      (node (ref "U$8") (pin "3") (pinfunction "VIN_3") (pintype "bidirectional"))
      (node (ref "VBAT") (pin "P$1") (pinfunction "PIN_P$1") (pintype "bidirectional"))
    )
    (net (code "68") (name "unconnected-(U$1-AT0-Pad26)") (class "Default")
      (node (ref "U$1") (pin "26") (pinfunction "AT0_26") (pintype "bidirectional"))
    )
    (net (code "69") (name "unconnected-(U$1-AT1-Pad27)") (class "Default")
      (node (ref "U$1") (pin "27") (pinfunction "AT1_27") (pintype "bidirectional"))
    )
    (net (code "70") (name "unconnected-(U$1-PA2-Pad11)") (class "Default")
      (node (ref "U$1") (pin "11") (pinfunction "PA2_11") (pintype "bidirectional"))
    )
    (net (code "71") (name "unconnected-(U$1-PA3-Pad12)") (class "Default")
      (node (ref "U$1") (pin "12") (pinfunction "PA3_12") (pintype "bidirectional"))
    )
    (net (code "72") (name "unconnected-(U$1-PA5-Pad14)") (class "Default")
      (node (ref "U$1") (pin "14") (pinfunction "PA5_14") (pintype "bidirectional"))
    )
    (net (code "73") (name "unconnected-(U$1-PA6-Pad15)") (class "Default")
      (node (ref "U$1") (pin "15") (pinfunction "PA6_15") (pintype "bidirectional"))
    )
    (net (code "74") (name "unconnected-(U$1-PA7-Pad16)") (class "Default")
      (node (ref "U$1") (pin "16") (pinfunction "PA7_16") (pintype "bidirectional"))
    )
    (net (code "75") (name "unconnected-(U$1-PA8-Pad17)") (class "Default")
      (node (ref "U$1") (pin "17") (pinfunction "PA8_17") (pintype "bidirectional"))
    )
    (net (code "76") (name "unconnected-(U$1-PA9-Pad18)") (class "Default")
      (node (ref "U$1") (pin "18") (pinfunction "PA9_18") (pintype "bidirectional"))
    )
    (net (code "77") (name "unconnected-(U$1-PA10-Pad36)") (class "Default")
      (node (ref "U$1") (pin "36") (pinfunction "PA10_36") (pintype "bidirectional"))
    )
    (net (code "78") (name "unconnected-(U$1-PA15-Pad42)") (class "Default")
      (node (ref "U$1") (pin "42") (pinfunction "PA15_42") (pintype "bidirectional"))
    )
    (net (code "79") (name "unconnected-(U$1-PB2-Pad19)") (class "Default")
      (node (ref "U$1") (pin "19") (pinfunction "PB2_19") (pintype "bidirectional"))
    )
    (net (code "80") (name "unconnected-(U$1-PB3-Pad43)") (class "Default")
      (node (ref "U$1") (pin "43") (pinfunction "PB3_43") (pintype "bidirectional"))
    )
    (net (code "81") (name "unconnected-(U$1-PB4-Pad44)") (class "Default")
      (node (ref "U$1") (pin "44") (pinfunction "PB4_44") (pintype "bidirectional"))
    )
    (net (code "82") (name "unconnected-(U$1-PB5-Pad45)") (class "Default")
      (node (ref "U$1") (pin "45") (pinfunction "PB5_45") (pintype "bidirectional"))
    )
    (net (code "83") (name "unconnected-(U$1-PB8-Pad5)") (class "Default")
      (node (ref "U$1") (pin "5") (pinfunction "PB8_5") (pintype "bidirectional"))
    )
    (net (code "84") (name "unconnected-(U$1-PB9-Pad6)") (class "Default")
      (node (ref "U$1") (pin "6") (pinfunction "PB9_6") (pintype "bidirectional"))
    )
    (net (code "85") (name "unconnected-(U$22-ID-PadP$11)") (class "Default")
      (node (ref "U$22") (pin "P$11") (pinfunction "ID_P$11") (pintype "bidirectional"))
    )
    (net (code "86") (name "unconnected-(U$24-IO0-Pad1)") (class "Default")
      (node (ref "U$24") (pin "1") (pinfunction "IO0_1") (pintype "bidirectional"))
    )
  )
)
